# Tasmodul_12V_Power_Manager.net
KiCad netlist of a schematic drawn in EAGLE
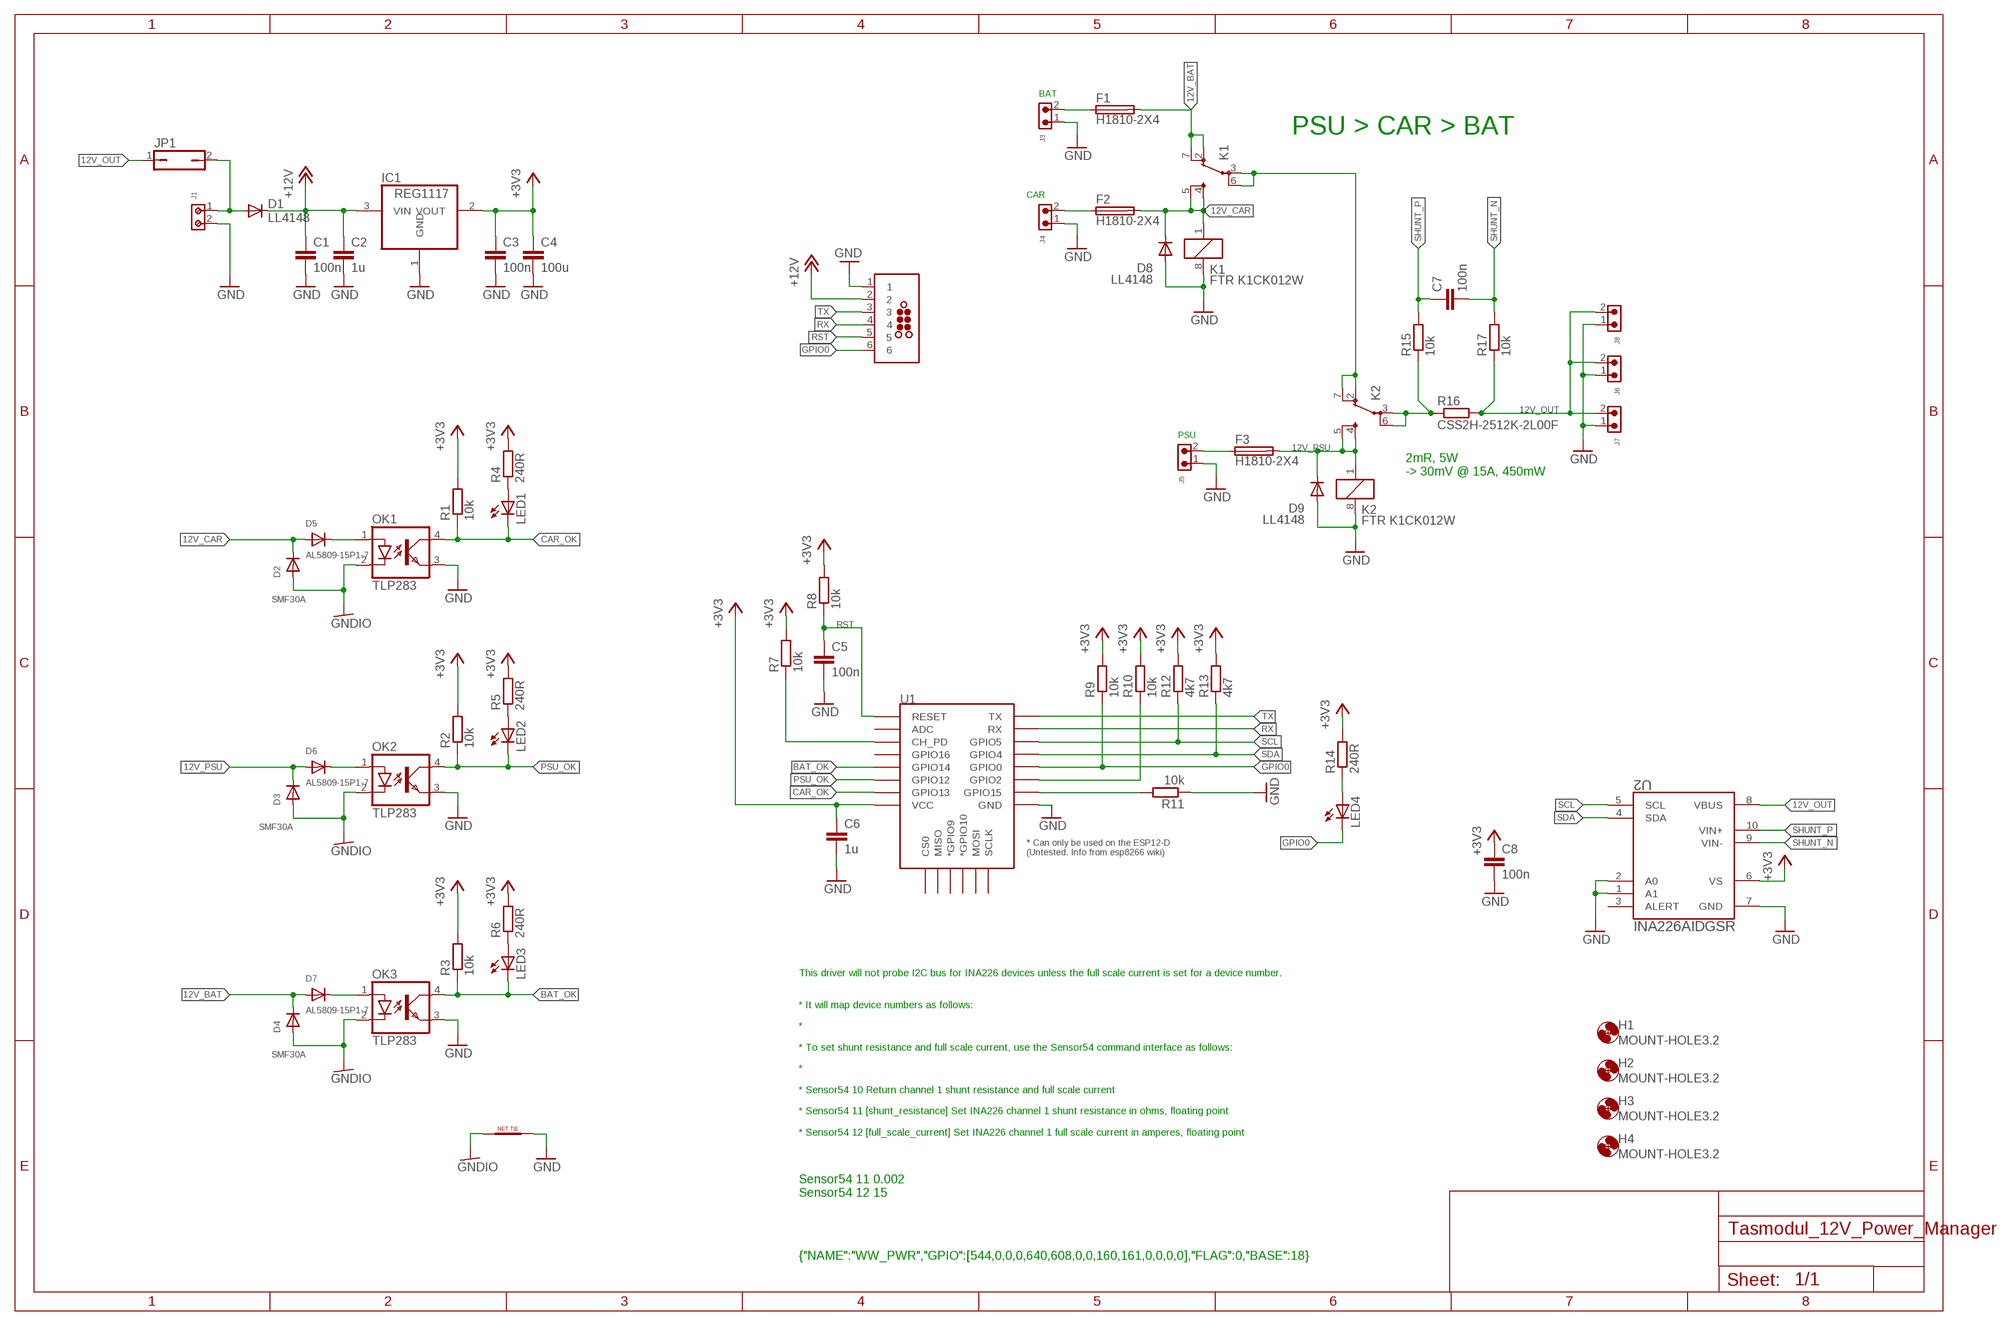
[diagram p0: schematic, sheet 1]

(export (version "E")
  (design (tool "Eeschema 10.0.6"))
  (components
    (comp (ref "C1")
      (value "100n")
      (footprint "eagle-import:C0603")
      (libsource (lib "eagle-import") (part "C-EUC0603"))
    )
    (comp (ref "C2")
      (value "1u")
      (footprint "eagle-import:C0603")
      (libsource (lib "eagle-import") (part "C-EUC0603"))
    )
    (comp (ref "C3")
      (value "100n")
      (footprint "eagle-import:C0603")
      (libsource (lib "eagle-import") (part "C-EUC0603"))
    )
    (comp (ref "C4")
      (value "100u")
      (footprint "eagle-import:C0603")
      (libsource (lib "eagle-import") (part "C-EUC0603"))
    )
    (comp (ref "C5")
      (value "100n")
      (footprint "eagle-import:C0603")
      (libsource (lib "eagle-import") (part "C-EUC0603"))
    )
    (comp (ref "C6")
      (value "1u")
      (footprint "eagle-import:C0603")
      (libsource (lib "eagle-import") (part "C-EUC0603"))
    )
    (comp (ref "C7")
      (value "100n")
      (footprint "eagle-import:C0603")
      (libsource (lib "eagle-import") (part "C-EUC0603"))
    )
    (comp (ref "C8")
      (value "100n")
      (footprint "eagle-import:C0603")
      (libsource (lib "eagle-import") (part "C-EUC0603"))
    )
    (comp (ref "D1")
      (value "LL4148")
      (footprint "eagle-import:MINIMELF")
      (libsource (lib "eagle-import") (part "DIODE-MINIMELF"))
    )
    (comp (ref "D2")
      (value "SMF30A")
      (footprint "eagle-import:SOD-123FL")
      (libsource (lib "eagle-import") (part "DIODE_SOD-123FL"))
    )
    (comp (ref "D3")
      (value "SMF30A")
      (footprint "eagle-import:SOD-123FL")
      (libsource (lib "eagle-import") (part "DIODE_SOD-123FL"))
    )
    (comp (ref "D4")
      (value "SMF30A")
      (footprint "eagle-import:SOD-123FL")
      (libsource (lib "eagle-import") (part "DIODE_SOD-123FL"))
    )
    (comp (ref "D5")
      (value "AL5809-15P1-7")
      (footprint "eagle-import:SOD-123FL")
      (libsource (lib "eagle-import") (part "DIODE_SOD-123FL"))
    )
    (comp (ref "D6")
      (value "AL5809-15P1-7")
      (footprint "eagle-import:SOD-123FL")
      (libsource (lib "eagle-import") (part "DIODE_SOD-123FL"))
    )
    (comp (ref "D7")
      (value "AL5809-15P1-7")
      (footprint "eagle-import:SOD-123FL")
      (libsource (lib "eagle-import") (part "DIODE_SOD-123FL"))
    )
    (comp (ref "D8")
      (value "LL4148")
      (footprint "eagle-import:MINIMELF")
      (libsource (lib "eagle-import") (part "DIODE-MINIMELF"))
    )
    (comp (ref "D9")
      (value "LL4148")
      (footprint "eagle-import:MINIMELF")
      (libsource (lib "eagle-import") (part "DIODE-MINIMELF"))
    )
    (comp (ref "F1")
      (value "H1810-2X4")
      (footprint "eagle-import:H1810-2X4")
      (libsource (lib "eagle-import") (part "H1810-2X4"))
    )
    (comp (ref "F2")
      (value "H1810-2X4")
      (footprint "eagle-import:H1810-2X4")
      (libsource (lib "eagle-import") (part "H1810-2X4"))
    )
    (comp (ref "F3")
      (value "H1810-2X4")
      (footprint "eagle-import:H1810-2X4")
      (libsource (lib "eagle-import") (part "H1810-2X4"))
    )
    (comp (ref "H1")
      (value "MOUNT-HOLE3.2")
      (footprint "eagle-import:3,2")
      (libsource (lib "eagle-import") (part "MOUNT-HOLE3.2"))
    )
    (comp (ref "H2")
      (value "MOUNT-HOLE3.2")
      (footprint "eagle-import:3,2")
      (libsource (lib "eagle-import") (part "MOUNT-HOLE3.2"))
    )
    (comp (ref "H3")
      (value "MOUNT-HOLE3.2")
      (footprint "eagle-import:3,2")
      (libsource (lib "eagle-import") (part "MOUNT-HOLE3.2"))
    )
    (comp (ref "H4")
      (value "MOUNT-HOLE3.2")
      (footprint "eagle-import:3,2")
      (libsource (lib "eagle-import") (part "MOUNT-HOLE3.2"))
    )
    (comp (ref "IC1")
      (value "REG1117")
      (footprint "eagle-import:SOT223")
      (libsource (lib "eagle-import") (part "REG1117"))
    )
    (comp (ref "J1")
      (value "691210910002")
      (footprint "eagle-import:691210910002")
      (libsource (lib "eagle-import") (part "691210910002"))
    )
    (comp (ref "J2")
      (value "TC2030-MCP-NL")
      (footprint "eagle-import:TC2030-MCP-NL")
      (libsource (lib "eagle-import") (part "TC2030-MCP-NL"))
    )
    (comp (ref "J3")
      (value "691313510002")
      (footprint "eagle-import:691313510002")
      (libsource (lib "eagle-import") (part "691313510002"))
    )
    (comp (ref "J4")
      (value "691313510002")
      (footprint "eagle-import:691313510002")
      (libsource (lib "eagle-import") (part "691313510002"))
    )
    (comp (ref "J5")
      (value "691313510002")
      (footprint "eagle-import:691313510002")
      (libsource (lib "eagle-import") (part "691313510002"))
    )
    (comp (ref "J6")
      (value "691313510002")
      (footprint "eagle-import:691313510002")
      (libsource (lib "eagle-import") (part "691313510002"))
    )
    (comp (ref "J7")
      (value "691313510002")
      (footprint "eagle-import:691313510002")
      (libsource (lib "eagle-import") (part "691313510002"))
    )
    (comp (ref "J8")
      (value "691313510002")
      (footprint "eagle-import:691313510002")
      (libsource (lib "eagle-import") (part "691313510002"))
    )
    (comp (ref "JP1")
      (value "JP1Q")
      (footprint "eagle-import:JP1")
      (libsource (lib "eagle-import") (part "JP1Q"))
    )
    (comp (ref "K1")
      (value "FTR K1CK012W")
      (footprint "eagle-import:FTR-K1C")
      (libsource (lib "eagle-import") (part "FTR-K1C"))
    )
    (comp (ref "K2")
      (value "FTR K1CK012W")
      (footprint "eagle-import:FTR-K1C")
      (libsource (lib "eagle-import") (part "FTR-K1C"))
    )
    (comp (ref "LED1")
      (value "LEDCHIP-LED0603")
      (footprint "eagle-import:CHIP-LED0603")
      (libsource (lib "eagle-import") (part "LEDCHIP-LED0603"))
    )
    (comp (ref "LED2")
      (value "LEDCHIP-LED0603")
      (footprint "eagle-import:CHIP-LED0603")
      (libsource (lib "eagle-import") (part "LEDCHIP-LED0603"))
    )
    (comp (ref "LED3")
      (value "LEDCHIP-LED0603")
      (footprint "eagle-import:CHIP-LED0603")
      (libsource (lib "eagle-import") (part "LEDCHIP-LED0603"))
    )
    (comp (ref "LED4")
      (value "LEDCHIP-LED0603")
      (footprint "eagle-import:CHIP-LED0603")
      (libsource (lib "eagle-import") (part "LEDCHIP-LED0603"))
    )
    (comp (ref "NT1")
      (value "NET_TIE0.5MM")
      (footprint "eagle-import:NET_TIE_0.5")
      (libsource (lib "eagle-import") (part "NET_TIE0.5MM"))
    )
    (comp (ref "OK1")
      (value "TLP283")
      (footprint "eagle-import:MINI-FLAT-4")
      (libsource (lib "eagle-import") (part "TLP283"))
    )
    (comp (ref "OK2")
      (value "TLP283")
      (footprint "eagle-import:MINI-FLAT-4")
      (libsource (lib "eagle-import") (part "TLP283"))
    )
    (comp (ref "OK3")
      (value "TLP283")
      (footprint "eagle-import:MINI-FLAT-4")
      (libsource (lib "eagle-import") (part "TLP283"))
    )
    (comp (ref "R1")
      (value "10k")
      (footprint "eagle-import:R0603")
      (libsource (lib "eagle-import") (part "R-EU_R0603"))
    )
    (comp (ref "R2")
      (value "10k")
      (footprint "eagle-import:R0603")
      (libsource (lib "eagle-import") (part "R-EU_R0603"))
    )
    (comp (ref "R3")
      (value "10k")
      (footprint "eagle-import:R0603")
      (libsource (lib "eagle-import") (part "R-EU_R0603"))
    )
    (comp (ref "R4")
      (value "240R")
      (footprint "eagle-import:R0603")
      (libsource (lib "eagle-import") (part "R-EU_R0603"))
    )
    (comp (ref "R5")
      (value "240R")
      (footprint "eagle-import:R0603")
      (libsource (lib "eagle-import") (part "R-EU_R0603"))
    )
    (comp (ref "R6")
      (value "240R")
      (footprint "eagle-import:R0603")
      (libsource (lib "eagle-import") (part "R-EU_R0603"))
    )
    (comp (ref "R7")
      (value "10k")
      (footprint "eagle-import:R0603")
      (libsource (lib "eagle-import") (part "R-EU_R0603"))
    )
    (comp (ref "R8")
      (value "10k")
      (footprint "eagle-import:R0603")
      (libsource (lib "eagle-import") (part "R-EU_R0603"))
    )
    (comp (ref "R9")
      (value "10k")
      (footprint "eagle-import:R0603")
      (libsource (lib "eagle-import") (part "R-EU_R0603"))
    )
    (comp (ref "R10")
      (value "10k")
      (footprint "eagle-import:R0603")
      (libsource (lib "eagle-import") (part "R-EU_R0603"))
    )
    (comp (ref "R11")
      (value "10k")
      (footprint "eagle-import:R0603")
      (libsource (lib "eagle-import") (part "R-EU_R0603"))
    )
    (comp (ref "R12")
      (value "4k7")
      (footprint "eagle-import:R0603")
      (libsource (lib "eagle-import") (part "R-EU_R0603"))
    )
    (comp (ref "R13")
      (value "4k7")
      (footprint "eagle-import:R0603")
      (libsource (lib "eagle-import") (part "R-EU_R0603"))
    )
    (comp (ref "R14")
      (value "240R")
      (footprint "eagle-import:R0603")
      (libsource (lib "eagle-import") (part "R-EU_R0603"))
    )
    (comp (ref "R15")
      (value "10k")
      (footprint "eagle-import:R0603")
      (libsource (lib "eagle-import") (part "R-EU_R0603"))
    )
    (comp (ref "R16")
      (value "CSS2H-2512K-2L00F")
      (footprint "eagle-import:CSS2H-2512K-2L00F")
      (libsource (lib "eagle-import") (part "CSS2H-2512K-2L00F"))
    )
    (comp (ref "R17")
      (value "10k")
      (footprint "eagle-import:R0603")
      (libsource (lib "eagle-import") (part "R-EU_R0603"))
    )
    (comp (ref "U1")
      (value "ESP12ESMD")
      (footprint "eagle-import:ESP12E-SMD")
      (libsource (lib "eagle-import") (part "ESP12ESMD"))
    )
    (comp (ref "U2")
      (value "INA226AIDGSR")
      (footprint "eagle-import:DGS10")
      (fields (field (name "COPYRIGHT") "Copyright (C) 2022 Ultra Librarian. All rights reserved."))
      (libsource (lib "eagle-import") (part "INA226AIDGSR"))
    )
  )
  (nets
    (net (code "1") (name "+3V3") (class "Default")
      (node (ref "C3") (pin "1") (pinfunction "1_1") (pintype "passive"))
      (node (ref "C4") (pin "1") (pinfunction "1_1") (pintype "passive"))
      (node (ref "C6") (pin "1") (pinfunction "1_1") (pintype "passive"))
      (node (ref "C8") (pin "1") (pinfunction "1_1") (pintype "passive"))
      (node (ref "IC1") (pin "2") (pinfunction "VOUT_2") (pintype "output"))
      (node (ref "R1") (pin "2") (pinfunction "2_2") (pintype "passive"))
      (node (ref "R10") (pin "2") (pinfunction "2_2") (pintype "passive"))
      (node (ref "R12") (pin "2") (pinfunction "2_2") (pintype "passive"))
      (node (ref "R13") (pin "2") (pinfunction "2_2") (pintype "passive"))
      (node (ref "R14") (pin "2") (pinfunction "2_2") (pintype "passive"))
      (node (ref "R2") (pin "2") (pinfunction "2_2") (pintype "passive"))
      (node (ref "R3") (pin "2") (pinfunction "2_2") (pintype "passive"))
      (node (ref "R4") (pin "2") (pinfunction "2_2") (pintype "passive"))
      (node (ref "R5") (pin "2") (pinfunction "2_2") (pintype "passive"))
      (node (ref "R6") (pin "2") (pinfunction "2_2") (pintype "passive"))
      (node (ref "R7") (pin "2") (pinfunction "2_2") (pintype "passive"))
      (node (ref "R8") (pin "2") (pinfunction "2_2") (pintype "passive"))
      (node (ref "R9") (pin "2") (pinfunction "2_2") (pintype "passive"))
      (node (ref "U1") (pin "VCC") (pinfunction "VCC_VCC") (pintype "bidirectional"))
      (node (ref "U2") (pin "6") (pinfunction "VS_6") (pintype "power_in"))
    )
    (net (code "2") (name "+12V") (class "Default")
      (node (ref "C1") (pin "1") (pinfunction "1_1") (pintype "passive"))
      (node (ref "C2") (pin "1") (pinfunction "1_1") (pintype "passive"))
      (node (ref "D1") (pin "C") (pinfunction "C_C") (pintype "passive"))
      (node (ref "IC1") (pin "3") (pinfunction "VIN_3") (pintype "input"))
      (node (ref "J2") (pin "2") (pinfunction "2_2") (pintype "power_in"))
    )
    (net (code "3") (name "12V_BAT") (class "Default")
      (node (ref "D4") (pin "C") (pinfunction "C_C") (pintype "passive"))
      (node (ref "D7") (pin "A") (pinfunction "A_A") (pintype "passive"))
      (node (ref "F1") (pin "B1") (pinfunction "2_B1") (pintype "passive"))
      (node (ref "F1") (pin "B2") (pinfunction "2_B2") (pintype "passive"))
      (node (ref "F1") (pin "B3") (pinfunction "2_B3") (pintype "passive"))
      (node (ref "F1") (pin "B4") (pinfunction "2_B4") (pintype "passive"))
      (node (ref "K1") (pin "2") (pinfunction "OA_2") (pintype "passive"))
      (node (ref "K1") (pin "7") (pinfunction "OB_7") (pintype "passive"))
    )
    (net (code "4") (name "12V_CAR") (class "Default")
      (node (ref "D2") (pin "C") (pinfunction "C_C") (pintype "passive"))
      (node (ref "D5") (pin "A") (pinfunction "A_A") (pintype "passive"))
      (node (ref "D8") (pin "C") (pinfunction "C_C") (pintype "passive"))
      (node (ref "F2") (pin "B1") (pinfunction "2_B1") (pintype "passive"))
      (node (ref "F2") (pin "B2") (pinfunction "2_B2") (pintype "passive"))
      (node (ref "F2") (pin "B3") (pinfunction "2_B3") (pintype "passive"))
      (node (ref "F2") (pin "B4") (pinfunction "2_B4") (pintype "passive"))
      (node (ref "K1") (pin "1") (pinfunction "1_1") (pintype "passive"))
      (node (ref "K1") (pin "4") (pinfunction "SA_4") (pintype "passive"))
      (node (ref "K1") (pin "5") (pinfunction "SB_5") (pintype "passive"))
    )
    (net (code "5") (name "12V_OUT") (class "Default")
      (node (ref "J6") (pin "2") (pinfunction "2_2") (pintype "passive"))
      (node (ref "J7") (pin "2") (pinfunction "2_2") (pintype "passive"))
      (node (ref "J8") (pin "2") (pinfunction "2_2") (pintype "passive"))
      (node (ref "JP1") (pin "1") (pinfunction "1_1") (pintype "passive"))
      (node (ref "R16") (pin "2") (pinfunction "2_2") (pintype "passive"))
      (node (ref "R17") (pin "1") (pinfunction "1_1") (pintype "passive"))
      (node (ref "U2") (pin "8") (pinfunction "VBUS_8") (pintype "input"))
    )
    (net (code "6") (name "12V_PSU") (class "Default")
      (node (ref "D3") (pin "C") (pinfunction "C_C") (pintype "passive"))
      (node (ref "D6") (pin "A") (pinfunction "A_A") (pintype "passive"))
      (node (ref "D9") (pin "C") (pinfunction "C_C") (pintype "passive"))
      (node (ref "F3") (pin "B1") (pinfunction "2_B1") (pintype "passive"))
      (node (ref "F3") (pin "B2") (pinfunction "2_B2") (pintype "passive"))
      (node (ref "F3") (pin "B3") (pinfunction "2_B3") (pintype "passive"))
      (node (ref "F3") (pin "B4") (pinfunction "2_B4") (pintype "passive"))
      (node (ref "K2") (pin "1") (pinfunction "1_1") (pintype "passive"))
      (node (ref "K2") (pin "4") (pinfunction "SA_4") (pintype "passive"))
      (node (ref "K2") (pin "5") (pinfunction "SB_5") (pintype "passive"))
    )
    (net (code "7") (name "BAT_OK") (class "Default")
      (node (ref "LED3") (pin "C") (pinfunction "C_C") (pintype "passive"))
      (node (ref "OK3") (pin "4") (pinfunction "COL_4") (pintype "passive"))
      (node (ref "R3") (pin "1") (pinfunction "1_1") (pintype "passive"))
      (node (ref "U1") (pin "GPIO14") (pinfunction "GPIO14_GPIO14") (pintype "bidirectional"))
    )
    (net (code "8") (name "CAR_OK") (class "Default")
      (node (ref "LED1") (pin "C") (pinfunction "C_C") (pintype "passive"))
      (node (ref "OK1") (pin "4") (pinfunction "COL_4") (pintype "passive"))
      (node (ref "R1") (pin "1") (pinfunction "1_1") (pintype "passive"))
      (node (ref "U1") (pin "GPIO13") (pinfunction "GPIO13_GPIO13") (pintype "bidirectional"))
    )
    (net (code "9") (name "GND") (class "Default")
      (node (ref "C1") (pin "2") (pinfunction "2_2") (pintype "passive"))
      (node (ref "C2") (pin "2") (pinfunction "2_2") (pintype "passive"))
      (node (ref "C3") (pin "2") (pinfunction "2_2") (pintype "passive"))
      (node (ref "C4") (pin "2") (pinfunction "2_2") (pintype "passive"))
      (node (ref "C5") (pin "2") (pinfunction "2_2") (pintype "passive"))
      (node (ref "C6") (pin "2") (pinfunction "2_2") (pintype "passive"))
      (node (ref "C8") (pin "2") (pinfunction "2_2") (pintype "passive"))
      (node (ref "D8") (pin "A") (pinfunction "A_A") (pintype "passive"))
      (node (ref "D9") (pin "A") (pinfunction "A_A") (pintype "passive"))
      (node (ref "IC1") (pin "1") (pinfunction "GND_1") (pintype "power_in"))
      (node (ref "J1") (pin "2") (pinfunction "2_2") (pintype "passive"))
      (node (ref "J2") (pin "1") (pinfunction "1_1") (pintype "passive"))
      (node (ref "J3") (pin "1") (pinfunction "1_1") (pintype "passive"))
      (node (ref "J4") (pin "1") (pinfunction "1_1") (pintype "passive"))
      (node (ref "J5") (pin "1") (pinfunction "1_1") (pintype "passive"))
      (node (ref "J6") (pin "1") (pinfunction "1_1") (pintype "passive"))
      (node (ref "J7") (pin "1") (pinfunction "1_1") (pintype "passive"))
      (node (ref "J8") (pin "1") (pinfunction "1_1") (pintype "passive"))
      (node (ref "K1") (pin "8") (pinfunction "2_8") (pintype "passive"))
      (node (ref "K2") (pin "8") (pinfunction "2_8") (pintype "passive"))
      (node (ref "NT1") (pin "NET2") (pinfunction "P$2_NET2") (pintype "bidirectional"))
      (node (ref "OK1") (pin "3") (pinfunction "EMIT_3") (pintype "passive"))
      (node (ref "OK2") (pin "3") (pinfunction "EMIT_3") (pintype "passive"))
      (node (ref "OK3") (pin "3") (pinfunction "EMIT_3") (pintype "passive"))
      (node (ref "R11") (pin "1") (pinfunction "1_1") (pintype "passive"))
      (node (ref "U1") (pin "GND") (pinfunction "GND_GND") (pintype "bidirectional"))
      (node (ref "U2") (pin "1") (pinfunction "A1_1") (pintype "passive"))
      (node (ref "U2") (pin "2") (pinfunction "A0_2") (pintype "passive"))
      (node (ref "U2") (pin "7") (pinfunction "GND_7") (pintype "power_in"))
    )
    (net (code "10") (name "GNDIO") (class "Default")
      (node (ref "D2") (pin "A") (pinfunction "A_A") (pintype "passive"))
      (node (ref "D3") (pin "A") (pinfunction "A_A") (pintype "passive"))
      (node (ref "D4") (pin "A") (pinfunction "A_A") (pintype "passive"))
      (node (ref "NT1") (pin "NET1") (pinfunction "P$1_NET1") (pintype "bidirectional"))
      (node (ref "OK1") (pin "2") (pinfunction "C_2") (pintype "passive"))
      (node (ref "OK2") (pin "2") (pinfunction "C_2") (pintype "passive"))
      (node (ref "OK3") (pin "2") (pinfunction "C_2") (pintype "passive"))
    )
    (net (code "11") (name "GPIO0") (class "Default")
      (node (ref "J2") (pin "6") (pinfunction "6_6") (pintype "bidirectional"))
      (node (ref "LED4") (pin "C") (pinfunction "C_C") (pintype "passive"))
      (node (ref "R9") (pin "1") (pinfunction "1_1") (pintype "passive"))
      (node (ref "U1") (pin "GPIO0") (pinfunction "GPIO0_GPIO0") (pintype "bidirectional"))
    )
    (net (code "12") (name "Net-(D1-PadA)") (class "Default")
      (node (ref "D1") (pin "A") (pinfunction "A_A") (pintype "passive"))
      (node (ref "J1") (pin "1") (pinfunction "1_1") (pintype "passive"))
      (node (ref "JP1") (pin "2") (pinfunction "2_2") (pintype "passive"))
    )
    (net (code "13") (name "Net-(F1-1-PadA1)") (class "Default")
      (node (ref "F1") (pin "A1") (pinfunction "1_A1") (pintype "passive"))
      (node (ref "F1") (pin "A2") (pinfunction "1_A2") (pintype "passive"))
      (node (ref "F1") (pin "A3") (pinfunction "1_A3") (pintype "passive"))
      (node (ref "F1") (pin "A4") (pinfunction "1_A4") (pintype "passive"))
      (node (ref "J3") (pin "2") (pinfunction "2_2") (pintype "passive"))
    )
    (net (code "14") (name "Net-(F2-1-PadA1)") (class "Default")
      (node (ref "F2") (pin "A1") (pinfunction "1_A1") (pintype "passive"))
      (node (ref "F2") (pin "A2") (pinfunction "1_A2") (pintype "passive"))
      (node (ref "F2") (pin "A3") (pinfunction "1_A3") (pintype "passive"))
      (node (ref "F2") (pin "A4") (pinfunction "1_A4") (pintype "passive"))
      (node (ref "J4") (pin "2") (pinfunction "2_2") (pintype "passive"))
    )
    (net (code "15") (name "Net-(F3-1-PadA1)") (class "Default")
      (node (ref "F3") (pin "A1") (pinfunction "1_A1") (pintype "passive"))
      (node (ref "F3") (pin "A2") (pinfunction "1_A2") (pintype "passive"))
      (node (ref "F3") (pin "A3") (pinfunction "1_A3") (pintype "passive"))
      (node (ref "F3") (pin "A4") (pinfunction "1_A4") (pintype "passive"))
      (node (ref "J5") (pin "2") (pinfunction "2_2") (pintype "passive"))
    )
    (net (code "16") (name "Net-(K1A-PA)") (class "Default")
      (node (ref "K1") (pin "3") (pinfunction "PA_3") (pintype "passive"))
      (node (ref "K1") (pin "6") (pinfunction "PB_6") (pintype "passive"))
      (node (ref "K2") (pin "2") (pinfunction "OA_2") (pintype "passive"))
      (node (ref "K2") (pin "7") (pinfunction "OB_7") (pintype "passive"))
    )
    (net (code "17") (name "Net-(K2A-PA)") (class "Default")
      (node (ref "K2") (pin "3") (pinfunction "PA_3") (pintype "passive"))
      (node (ref "K2") (pin "6") (pinfunction "PB_6") (pintype "passive"))
      (node (ref "R15") (pin "1") (pinfunction "1_1") (pintype "passive"))
      (node (ref "R16") (pin "1") (pinfunction "1_1") (pintype "passive"))
    )
    (net (code "18") (name "Net-(LED1-PadA)") (class "Default")
      (node (ref "LED1") (pin "A") (pinfunction "A_A") (pintype "passive"))
      (node (ref "R4") (pin "1") (pinfunction "1_1") (pintype "passive"))
    )
    (net (code "19") (name "Net-(LED2-PadA)") (class "Default")
      (node (ref "LED2") (pin "A") (pinfunction "A_A") (pintype "passive"))
      (node (ref "R5") (pin "1") (pinfunction "1_1") (pintype "passive"))
    )
    (net (code "20") (name "Net-(LED3-PadA)") (class "Default")
      (node (ref "LED3") (pin "A") (pinfunction "A_A") (pintype "passive"))
      (node (ref "R6") (pin "1") (pinfunction "1_1") (pintype "passive"))
    )
    (net (code "21") (name "Net-(LED4-PadA)") (class "Default")
      (node (ref "LED4") (pin "A") (pinfunction "A_A") (pintype "passive"))
      (node (ref "R14") (pin "1") (pinfunction "1_1") (pintype "passive"))
    )
    (net (code "22") (name "Net-(OK1-A)") (class "Default")
      (node (ref "D5") (pin "C") (pinfunction "C_C") (pintype "passive"))
      (node (ref "OK1") (pin "1") (pinfunction "A_1") (pintype "passive"))
    )
    (net (code "23") (name "Net-(OK2-A)") (class "Default")
      (node (ref "D6") (pin "C") (pinfunction "C_C") (pintype "passive"))
      (node (ref "OK2") (pin "1") (pinfunction "A_1") (pintype "passive"))
    )
    (net (code "24") (name "Net-(OK3-A)") (class "Default")
      (node (ref "D7") (pin "C") (pinfunction "C_C") (pintype "passive"))
      (node (ref "OK3") (pin "1") (pinfunction "A_1") (pintype "passive"))
    )
    (net (code "25") (name "Net-(R7-Pad1)") (class "Default")
      (node (ref "R7") (pin "1") (pinfunction "1_1") (pintype "passive"))
      (node (ref "U1") (pin "CH_PD") (pinfunction "CH_PD_CH_PD") (pintype "bidirectional"))
    )
    (net (code "26") (name "Net-(R10-Pad1)") (class "Default")
      (node (ref "R10") (pin "1") (pinfunction "1_1") (pintype "passive"))
      (node (ref "U1") (pin "GPIO2") (pinfunction "GPIO2_GPIO2") (pintype "bidirectional"))
    )
    (net (code "27") (name "Net-(R11-Pad2)") (class "Default")
      (node (ref "R11") (pin "2") (pinfunction "2_2") (pintype "passive"))
      (node (ref "U1") (pin "GPIO15") (pinfunction "GPIO15_GPIO15") (pintype "bidirectional"))
    )
    (net (code "28") (name "PSU_OK") (class "Default")
      (node (ref "LED2") (pin "C") (pinfunction "C_C") (pintype "passive"))
      (node (ref "OK2") (pin "4") (pinfunction "COL_4") (pintype "passive"))
      (node (ref "R2") (pin "1") (pinfunction "1_1") (pintype "passive"))
      (node (ref "U1") (pin "GPIO12") (pinfunction "GPIO12_GPIO12") (pintype "bidirectional"))
    )
    (net (code "29") (name "RST") (class "Default")
      (node (ref "C5") (pin "1") (pinfunction "1_1") (pintype "passive"))
      (node (ref "J2") (pin "5") (pinfunction "5_5") (pintype "output"))
      (node (ref "R8") (pin "1") (pinfunction "1_1") (pintype "passive"))
      (node (ref "U1") (pin "RESET") (pinfunction "RESET_RESET") (pintype "bidirectional"))
    )
    (net (code "30") (name "RX") (class "Default")
      (node (ref "J2") (pin "4") (pinfunction "4_4") (pintype "bidirectional"))
      (node (ref "U1") (pin "RXD0") (pinfunction "RX_RXD0") (pintype "bidirectional"))
    )
    (net (code "31") (name "SCL") (class "Default")
      (node (ref "R12") (pin "1") (pinfunction "1_1") (pintype "passive"))
      (node (ref "U1") (pin "GPIO5") (pinfunction "GPIO5_GPIO5") (pintype "bidirectional"))
      (node (ref "U2") (pin "5") (pinfunction "SCL_5") (pintype "input"))
    )
    (net (code "32") (name "SDA") (class "Default")
      (node (ref "R13") (pin "1") (pinfunction "1_1") (pintype "passive"))
      (node (ref "U1") (pin "GPIO4") (pinfunction "GPIO4_GPIO4") (pintype "bidirectional"))
      (node (ref "U2") (pin "4") (pinfunction "SDA_4") (pintype "bidirectional"))
    )
    (net (code "33") (name "SHUNT_N") (class "Default")
      (node (ref "C7") (pin "2") (pinfunction "2_2") (pintype "passive"))
      (node (ref "R17") (pin "2") (pinfunction "2_2") (pintype "passive"))
      (node (ref "U2") (pin "9") (pinfunction "VIN-_9") (pintype "input"))
    )
    (net (code "34") (name "SHUNT_P") (class "Default")
      (node (ref "C7") (pin "1") (pinfunction "1_1") (pintype "passive"))
      (node (ref "R15") (pin "2") (pinfunction "2_2") (pintype "passive"))
      (node (ref "U2") (pin "10") (pinfunction "VIN+_10") (pintype "input"))
    )
    (net (code "35") (name "TX") (class "Default")
      (node (ref "J2") (pin "3") (pinfunction "3_3") (pintype "power_in"))
      (node (ref "U1") (pin "TXD0") (pinfunction "TX_TXD0") (pintype "bidirectional"))
    )
    (net (code "36") (name "unconnected-(U1-*GPIO9-PadGPIO9)") (class "Default")
      (node (ref "U1") (pin "GPIO9") (pinfunction "*GPIO9_GPIO9") (pintype "bidirectional"))
    )
    (net (code "37") (name "unconnected-(U1-*GPIO10-PadGPIO10)") (class "Default")
      (node (ref "U1") (pin "GPIO10") (pinfunction "*GPIO10_GPIO10") (pintype "bidirectional"))
    )
    (net (code "38") (name "unconnected-(U1-PadADC)") (class "Default")
      (node (ref "U1") (pin "ADC") (pinfunction "ADC_ADC") (pintype "bidirectional"))
    )
    (net (code "39") (name "unconnected-(U1-PadCS0)") (class "Default")
      (node (ref "U1") (pin "CS0") (pinfunction "CS0_CS0") (pintype "bidirectional"))
    )
    (net (code "40") (name "unconnected-(U1-PadGPIO16)") (class "Default")
      (node (ref "U1") (pin "GPIO16") (pinfunction "GPIO16_GPIO16") (pintype "bidirectional"))
    )
    (net (code "41") (name "unconnected-(U1-PadMISO)") (class "Default")
      (node (ref "U1") (pin "MISO") (pinfunction "MISO_MISO") (pintype "bidirectional"))
    )
    (net (code "42") (name "unconnected-(U1-PadMOSI)") (class "Default")
      (node (ref "U1") (pin "MOSI") (pinfunction "MOSI_MOSI") (pintype "bidirectional"))
    )
    (net (code "43") (name "unconnected-(U1-PadSCLK)") (class "Default")
      (node (ref "U1") (pin "SCLK") (pinfunction "SCLK_SCLK") (pintype "bidirectional"))
    )
    (net (code "44") (name "unconnected-(U2-ALERT-Pad3)") (class "Default")
      (node (ref "U2") (pin "3") (pinfunction "ALERT_3") (pintype "output"))
    )
  )
)
